# switch_hub.net
KiCad netlist of a schematic drawn in EAGLE
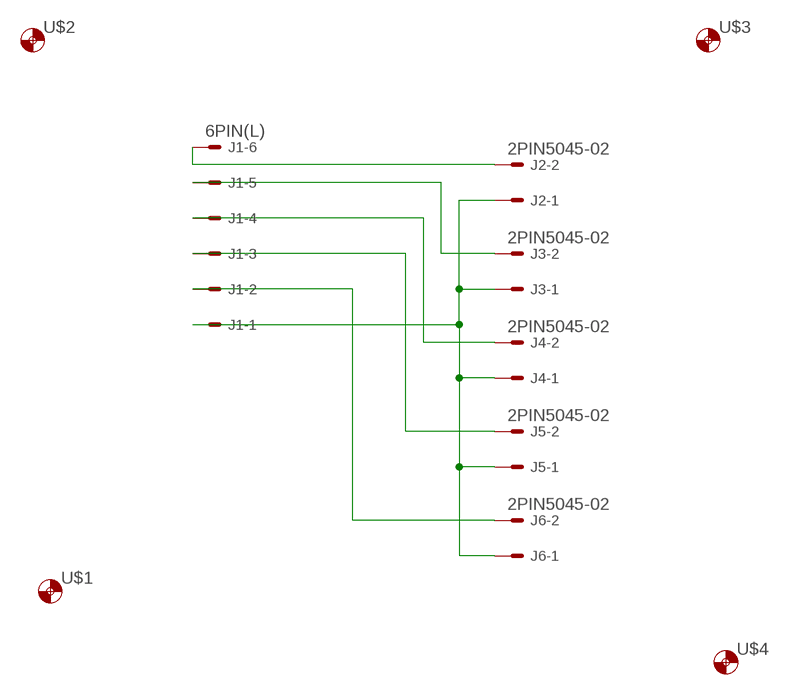
[diagram p0: schematic, sheet 1]

(export (version "E")
  (design (tool "Eeschema 10.0.6"))
  (components
    (comp (ref "J1")
      (value "6PIN(L)")
      (footprint "eagle-import:6PL")
      (libsource (lib "eagle-import") (part "6PIN(L)"))
    )
    (comp (ref "J2")
      (value "2PIN5045-02")
      (footprint "eagle-import:5045-02")
      (libsource (lib "eagle-import") (part "2PIN5045-02"))
    )
    (comp (ref "J3")
      (value "2PIN5045-02")
      (footprint "eagle-import:5045-02")
      (libsource (lib "eagle-import") (part "2PIN5045-02"))
    )
    (comp (ref "J4")
      (value "2PIN5045-02")
      (footprint "eagle-import:5045-02")
      (libsource (lib "eagle-import") (part "2PIN5045-02"))
    )
    (comp (ref "J5")
      (value "2PIN5045-02")
      (footprint "eagle-import:5045-02")
      (libsource (lib "eagle-import") (part "2PIN5045-02"))
    )
    (comp (ref "J6")
      (value "2PIN5045-02")
      (footprint "eagle-import:5045-02")
      (libsource (lib "eagle-import") (part "2PIN5045-02"))
    )
    (comp (ref "U$1")
      (value "1MMDRILL")
      (footprint "eagle-import:1MDRILL")
      (libsource (lib "eagle-import") (part "1MMDRILL"))
    )
    (comp (ref "U$2")
      (value "1MMDRILL")
      (footprint "eagle-import:1MDRILL")
      (libsource (lib "eagle-import") (part "1MMDRILL"))
    )
    (comp (ref "U$3")
      (value "1MMDRILL")
      (footprint "eagle-import:1MDRILL")
      (libsource (lib "eagle-import") (part "1MMDRILL"))
    )
    (comp (ref "U$4")
      (value "1MMDRILL")
      (footprint "eagle-import:1MDRILL")
      (libsource (lib "eagle-import") (part "1MMDRILL"))
    )
  )
  (nets
    (net (code "1") (name "Net-(J1A-S)") (class "Default")
      (node (ref "J1") (pin "1") (pinfunction "S_1") (pintype "passive"))
      (node (ref "J2") (pin "P$2") (pinfunction "S_P$2") (pintype "passive"))
      (node (ref "J3") (pin "P$2") (pinfunction "S_P$2") (pintype "passive"))
      (node (ref "J4") (pin "P$2") (pinfunction "S_P$2") (pintype "passive"))
      (node (ref "J5") (pin "P$2") (pinfunction "S_P$2") (pintype "passive"))
      (node (ref "J6") (pin "P$2") (pinfunction "S_P$2") (pintype "passive"))
    )
    (net (code "2") (name "Net-(J1B-S)") (class "Default")
      (node (ref "J1") (pin "2") (pinfunction "S_2") (pintype "passive"))
      (node (ref "J6") (pin "P$1") (pinfunction "S_P$1") (pintype "passive"))
    )
    (net (code "3") (name "Net-(J1C-S)") (class "Default")
      (node (ref "J1") (pin "3") (pinfunction "S_3") (pintype "passive"))
      (node (ref "J5") (pin "P$1") (pinfunction "S_P$1") (pintype "passive"))
    )
    (net (code "4") (name "Net-(J1D-S)") (class "Default")
      (node (ref "J1") (pin "4") (pinfunction "S_4") (pintype "passive"))
      (node (ref "J4") (pin "P$1") (pinfunction "S_P$1") (pintype "passive"))
    )
    (net (code "5") (name "Net-(J1E-S)") (class "Default")
      (node (ref "J1") (pin "5") (pinfunction "S_5") (pintype "passive"))
      (node (ref "J3") (pin "P$1") (pinfunction "S_P$1") (pintype "passive"))
    )
    (net (code "6") (name "Net-(J1F-S)") (class "Default")
      (node (ref "J1") (pin "6") (pinfunction "S_6") (pintype "passive"))
      (node (ref "J2") (pin "P$1") (pinfunction "S_P$1") (pintype "passive"))
    )
  )
)
